# PowerSupply.net
KiCad netlist of a schematic drawn in Altium Designer
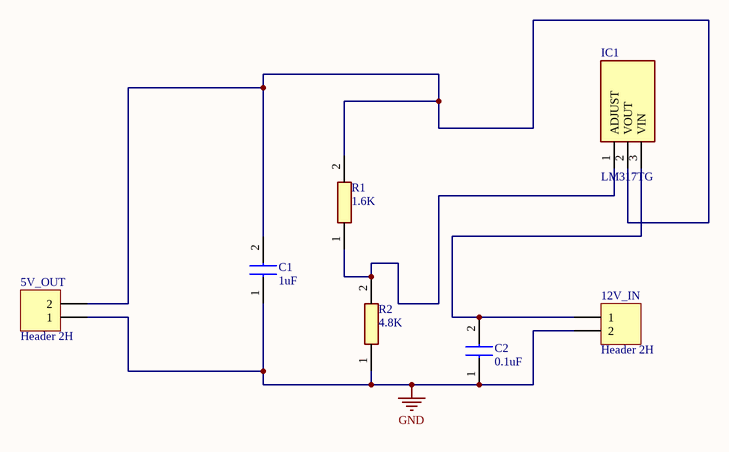
[diagram p0: PowerSupply.SchDoc]

(export (version "E")
  (design (tool "Eeschema 10.0.6"))
  (components
    (comp (ref "5V_OUT")
      (value "Header 2H")
      (footprint "HDR1X2H")
      (description "Header, 2-Pin, Right Angle")
      (fields (field (name "PUBLISHER") "Altium Limited"))
      (libsource (lib "Miscellaneous Connectors") (part "Header 2H"))
    )
    (comp (ref "12V_IN")
      (value "Header 2H")
      (footprint "HDR1X2H")
      (description "Header, 2-Pin, Right Angle")
      (fields (field (name "PUBLISHER") "Altium Limited"))
      (libsource (lib "") (part "Header 2H_1"))
    )
    (comp (ref "C1")
      (value "1uF")
      (footprint "SamacSys:CAPC2012X145N")
      (description "Capacitor")
      (fields
        (field (name "MANUFACTURER_PART_NUMBER") "CGA4J1X8L1H105K125AE")
        (field (name "MOUSER PART NUMBER") "810-CGA4J1X8L1H10512")
      )
      (libsource (lib "*") (part "CGA4J1X8L1H105K125AE"))
    )
    (comp (ref "C2")
      (value "0.1uF")
      (footprint "SamacSys:CAPC2012X88N")
      (description "Capacitor")
      (fields
        (field (name "MANUFACTURER_PART_NUMBER") "C0805C104K8RACAUTO")
        (field (name "MOUSER PART NUMBER") "80-C0805C104K8RAUTO")
      )
      (libsource (lib "*") (part "C0805C104K8RACAUTO"))
    )
    (comp (ref "IC1")
      (value "LM317TG")
      (footprint "SamacSys:TO254P482X997X2018-3P")
      (description "Integrated Circuit")
      (fields (field (name "MOUSER PART NUMBER") "863-LM317TG"))
      (libsource (lib "*") (part "LM317TG"))
    )
    (comp (ref "R1")
      (value "1.6K")
      (footprint "SamacSys:ERA6A_(0805)")
      (description "Resistor")
      (fields
        (field (name "MANUFACTURER_PART_NUMBER") "ERA-6ARB162V")
        (field (name "MOUSER PART NUMBER") "667-ERA-6ARB162V")
      )
      (libsource (lib "*") (part "ERA-6ARB162V"))
    )
    (comp (ref "R2")
      (value "4.8K")
      (footprint "SamacSys:ERA6VK")
      (description "Resistor")
      (fields
        (field (name "MANUFACTURER_PART_NUMBER") "ERA-6VEB4702V")
        (field (name "MOUSER PART NUMBER") "667-ERA-6VEB4702V")
      )
      (libsource (lib "*") (part "ERA-6VEB4702V"))
    )
  )
  (nets
    (net (code "1") (name "GND") (class "Default")
      (node (ref "12V_IN") (pin "2") (pinfunction "2_2") (pintype "passive"))
      (node (ref "5V_OUT") (pin "1") (pinfunction "1_1") (pintype "passive"))
      (node (ref "C1") (pin "1") (pinfunction "1_1") (pintype "passive"))
      (node (ref "C2") (pin "1") (pinfunction "1_1") (pintype "passive"))
      (node (ref "R2") (pin "1") (pinfunction "1_1") (pintype "passive"))
    )
    (net (code "2") (name "Net-(IC1-ADJUST)") (class "Default")
      (node (ref "IC1") (pin "1") (pinfunction "ADJUST_1") (pintype "passive"))
      (node (ref "R1") (pin "1") (pinfunction "1_1") (pintype "passive"))
      (node (ref "R2") (pin "2") (pinfunction "2_2") (pintype "passive"))
    )
    (net (code "3") (name "Net-(IC1-VIN)") (class "Default")
      (node (ref "12V_IN") (pin "1") (pinfunction "1_1") (pintype "passive"))
      (node (ref "C2") (pin "2") (pinfunction "2_2") (pintype "passive"))
      (node (ref "IC1") (pin "3") (pinfunction "VIN_3") (pintype "passive"))
    )
    (net (code "4") (name "Net-(IC1-VOUT)") (class "Default")
      (node (ref "5V_OUT") (pin "2") (pinfunction "2_2") (pintype "passive"))
      (node (ref "C1") (pin "2") (pinfunction "2_2") (pintype "passive"))
      (node (ref "IC1") (pin "2") (pinfunction "VOUT_2") (pintype "passive"))
      (node (ref "R1") (pin "2") (pinfunction "2_2") (pintype "passive"))
    )
  )
)
